# atxflip.net
KiCad netlist of a schematic drawn in EAGLE
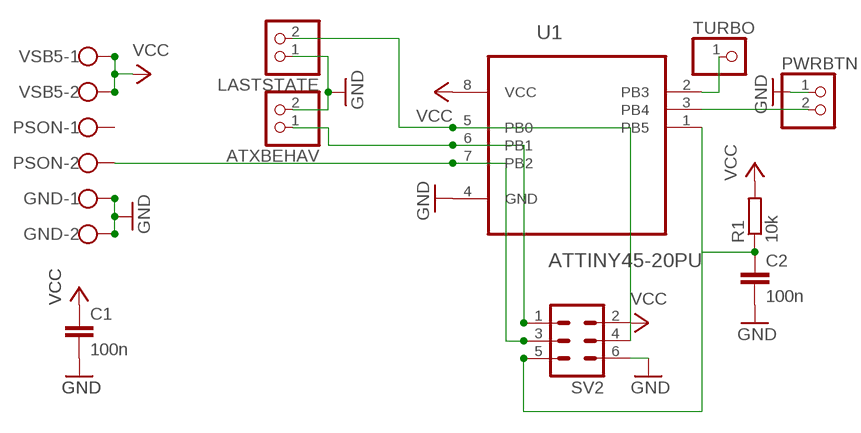
[diagram p0: schematic, sheet 1]

(export (version "E")
  (design (tool "Eeschema 10.0.6"))
  (components
    (comp (ref "ATXBEHAV")
      (value "PINHD-1X2")
      (footprint "eagle-import:1X02")
      (libsource (lib "eagle-import") (part "PINHD-1X2"))
    )
    (comp (ref "C1")
      (value "100n")
      (footprint "eagle-import:C7.5B3")
      (libsource (lib "eagle-import") (part "C7.5/3"))
    )
    (comp (ref "C2")
      (value "100n")
      (footprint "eagle-import:C7.5B3")
      (libsource (lib "eagle-import") (part "C7.5/3"))
    )
    (comp (ref "GND")
      (value "W237-102")
      (footprint "eagle-import:W237-102")
      (fields (field (name "MPN") "237-102"))
      (libsource (lib "eagle-import") (part "W237-102"))
    )
    (comp (ref "LASTSTATE")
      (value "PINHD-1X2")
      (footprint "eagle-import:1X02")
      (libsource (lib "eagle-import") (part "PINHD-1X2"))
    )
    (comp (ref "PSON")
      (value "W237-102")
      (footprint "eagle-import:W237-102")
      (fields (field (name "MPN") "237-102"))
      (libsource (lib "eagle-import") (part "W237-102"))
    )
    (comp (ref "PWRBTN")
      (value "PINHD-1X2")
      (footprint "eagle-import:1X02")
      (libsource (lib "eagle-import") (part "PINHD-1X2"))
    )
    (comp (ref "R1")
      (value "10k")
      (footprint "eagle-import:0207_10")
      (libsource (lib "eagle-import") (part "R-EU_0207/10"))
    )
    (comp (ref "SV2")
      (value "ML6")
      (footprint "eagle-import:ML6")
      (libsource (lib "eagle-import") (part "ML6"))
    )
    (comp (ref "TURBO")
      (value "PINHD-1X1")
      (footprint "eagle-import:1X01")
      (libsource (lib "eagle-import") (part "PINHD-1X1"))
    )
    (comp (ref "U1")
      (value "ATTINY45-20PU")
      (footprint "eagle-import:DIP254P762X533-8")
      (libsource (lib "eagle-import") (part "ATTINY45-20PU"))
    )
    (comp (ref "VSB5")
      (value "W237-102")
      (footprint "eagle-import:W237-102")
      (fields (field (name "MPN") "237-102"))
      (libsource (lib "eagle-import") (part "W237-102"))
    )
  )
  (nets
    (net (code "1") (name "GND") (class "Default")
      (node (ref "ATXBEHAV") (pin "2") (pinfunction "2_2") (pintype "passive"))
      (node (ref "C1") (pin "2") (pinfunction "2_2") (pintype "passive"))
      (node (ref "C2") (pin "2") (pinfunction "2_2") (pintype "passive"))
      (node (ref "GND") (pin "1") (pinfunction "KL_1") (pintype "passive"))
      (node (ref "GND") (pin "2") (pinfunction "KL_2") (pintype "passive"))
      (node (ref "LASTSTATE") (pin "1") (pinfunction "1_1") (pintype "passive"))
      (node (ref "PWRBTN") (pin "1") (pinfunction "1_1") (pintype "passive"))
      (node (ref "SV2") (pin "6") (pinfunction "6_6") (pintype "passive"))
      (node (ref "U1") (pin "4") (pinfunction "GND_4") (pintype "passive"))
    )
    (net (code "2") (name "Net-(PSONB-KL)") (class "Default")
      (node (ref "PSON") (pin "2") (pinfunction "KL_2") (pintype "passive"))
      (node (ref "SV2") (pin "3") (pinfunction "3_3") (pintype "passive"))
      (node (ref "U1") (pin "7") (pinfunction "PB2_7") (pintype "bidirectional"))
    )
    (net (code "3") (name "Net-(U1-PB0)") (class "Default")
      (node (ref "LASTSTATE") (pin "2") (pinfunction "2_2") (pintype "passive"))
      (node (ref "SV2") (pin "4") (pinfunction "4_4") (pintype "passive"))
      (node (ref "U1") (pin "5") (pinfunction "PB0_5") (pintype "bidirectional"))
    )
    (net (code "4") (name "Net-(U1-PB1)") (class "Default")
      (node (ref "ATXBEHAV") (pin "1") (pinfunction "1_1") (pintype "passive"))
      (node (ref "SV2") (pin "1") (pinfunction "1_1") (pintype "passive"))
      (node (ref "U1") (pin "6") (pinfunction "PB1_6") (pintype "bidirectional"))
    )
    (net (code "5") (name "Net-(U1-PB3)") (class "Default")
      (node (ref "TURBO") (pin "1") (pinfunction "1_1") (pintype "passive"))
      (node (ref "U1") (pin "2") (pinfunction "PB3_2") (pintype "bidirectional"))
    )
    (net (code "6") (name "Net-(U1-PB4)") (class "Default")
      (node (ref "PWRBTN") (pin "2") (pinfunction "2_2") (pintype "passive"))
      (node (ref "U1") (pin "3") (pinfunction "PB4_3") (pintype "bidirectional"))
    )
    (net (code "7") (name "Net-(U1-PB5)") (class "Default")
      (node (ref "C2") (pin "1") (pinfunction "1_1") (pintype "passive"))
      (node (ref "R1") (pin "1") (pinfunction "1_1") (pintype "passive"))
      (node (ref "SV2") (pin "5") (pinfunction "5_5") (pintype "passive"))
      (node (ref "U1") (pin "1") (pinfunction "PB5_1") (pintype "bidirectional"))
    )
    (net (code "8") (name "VCC") (class "Default")
      (node (ref "C1") (pin "1") (pinfunction "1_1") (pintype "passive"))
      (node (ref "R1") (pin "2") (pinfunction "2_2") (pintype "passive"))
      (node (ref "SV2") (pin "2") (pinfunction "2_2") (pintype "passive"))
      (node (ref "U1") (pin "8") (pinfunction "VCC_8") (pintype "power_in"))
      (node (ref "VSB5") (pin "1") (pinfunction "KL_1") (pintype "passive"))
      (node (ref "VSB5") (pin "2") (pinfunction "KL_2") (pintype "passive"))
    )
    (net (code "9") (name "unconnected-(PSONA-KL-Pad1)") (class "Default")
      (node (ref "PSON") (pin "1") (pinfunction "KL_1") (pintype "passive"))
    )
  )
)
